# ogn_wind_1_4.net
KiCad netlist of a schematic drawn in EAGLE
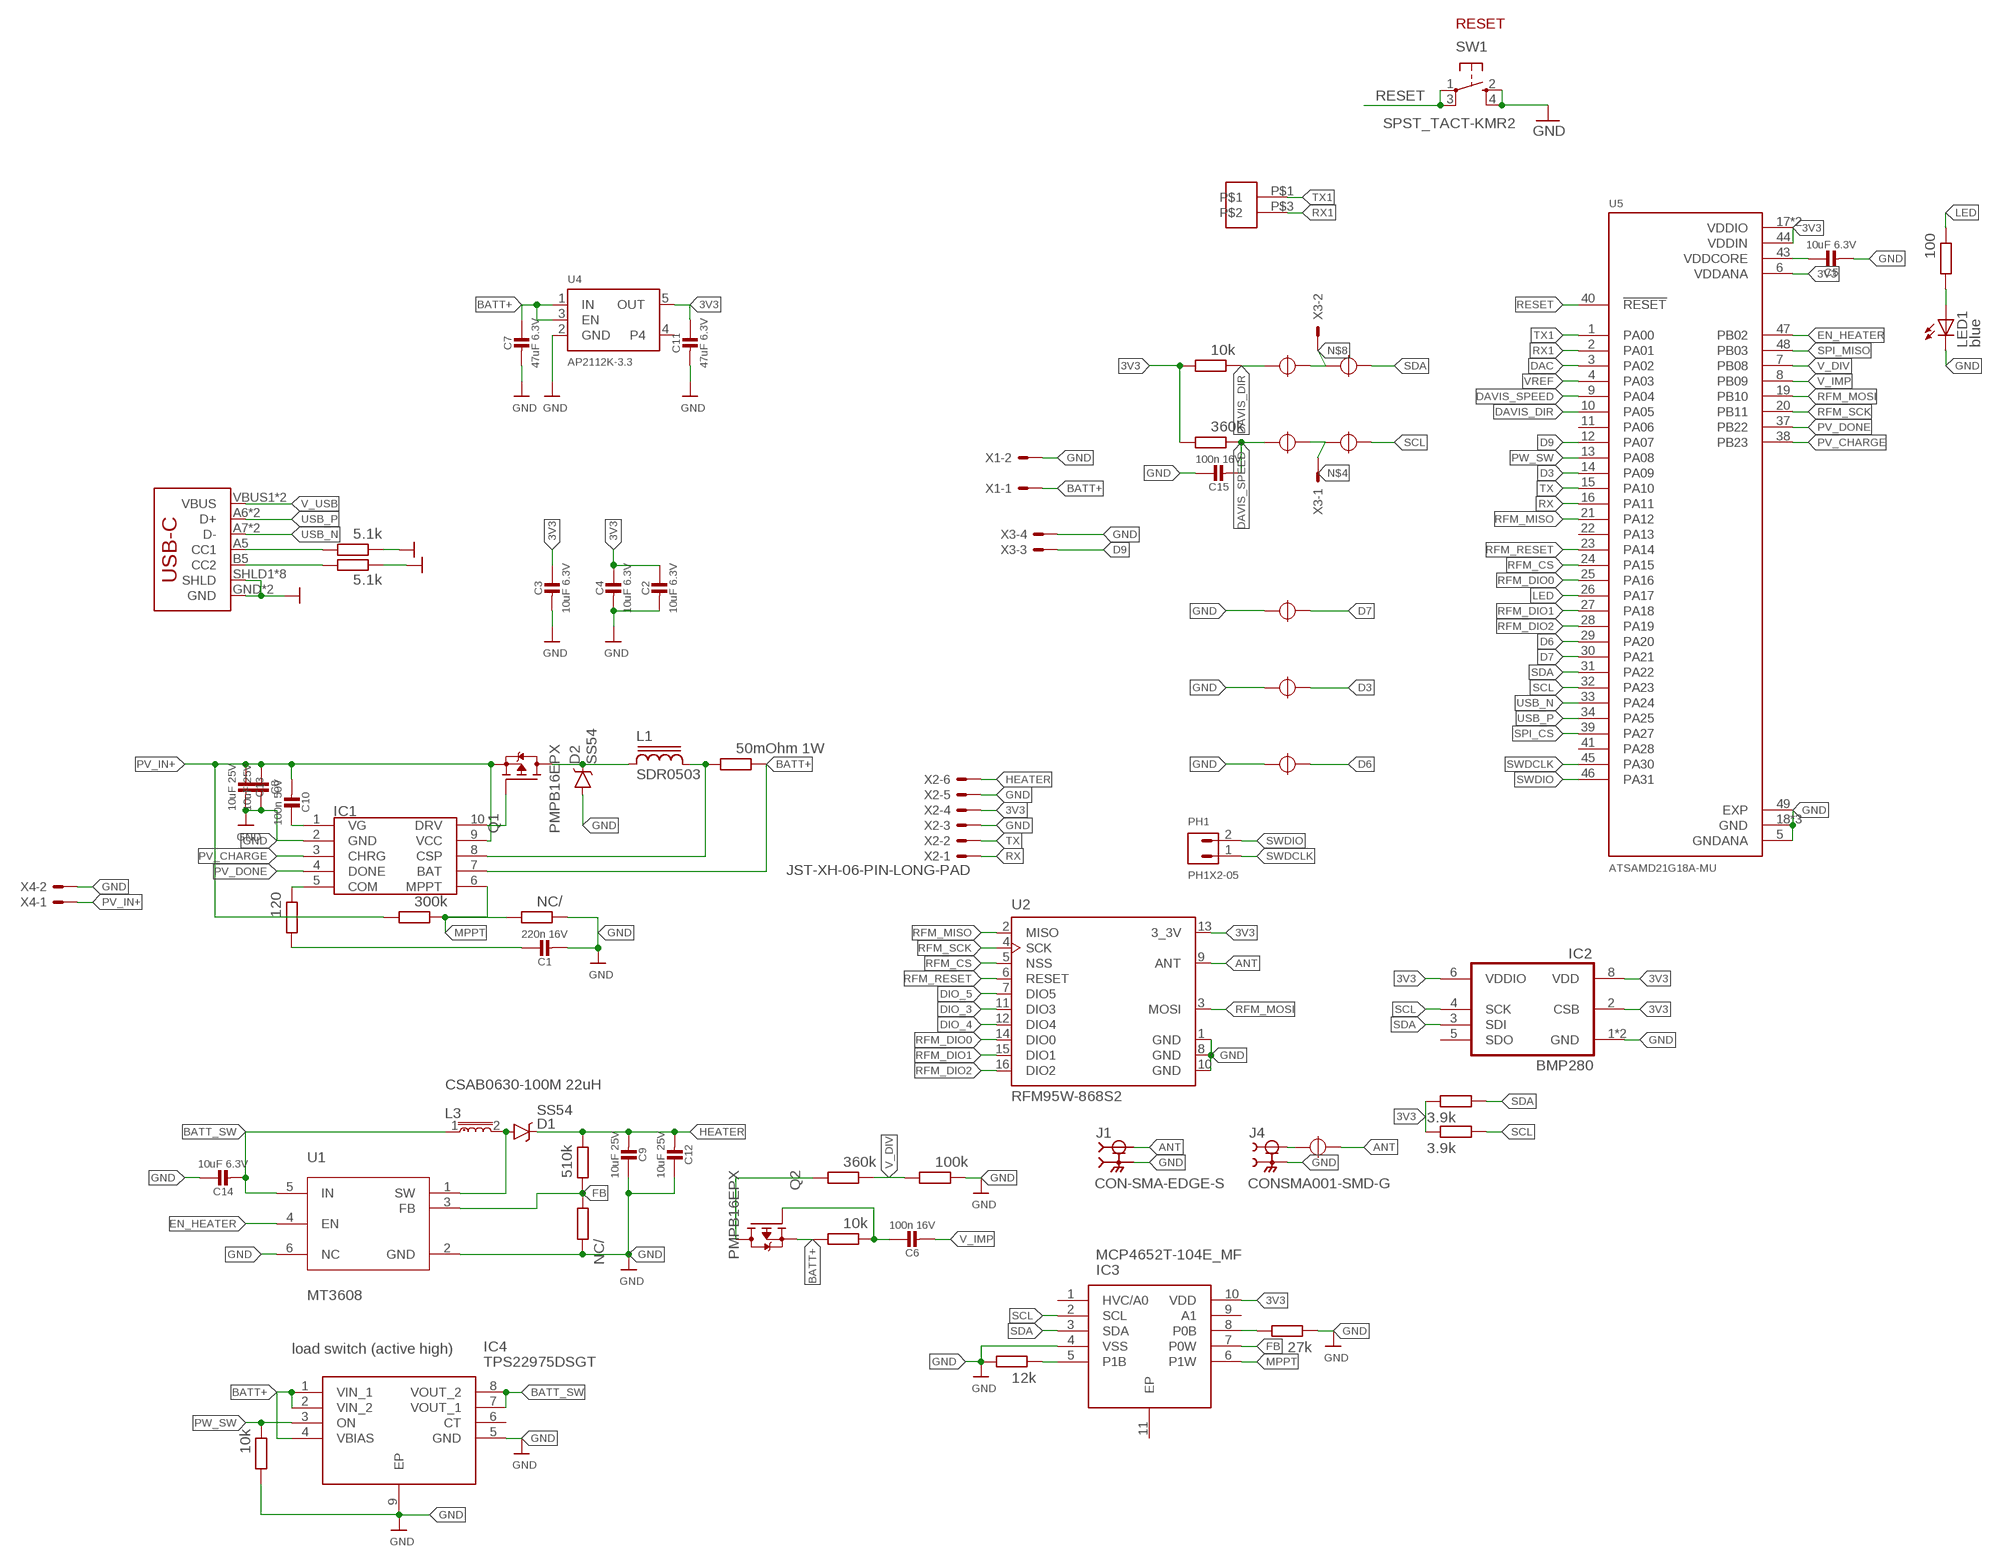
[diagram p0: schematic, sheet 1]

(export (version "E")
  (design (tool "Eeschema 10.0.6"))
  (components
    (comp (ref "C1")
      (value "220n 16V")
      (footprint "eagle-import:_0402MP")
      (libsource (lib "eagle-import") (part "CAP_CERAMIC_0402MP"))
    )
    (comp (ref "C2")
      (value "10uF 6.3V")
      (footprint "eagle-import:_0402MP")
      (libsource (lib "eagle-import") (part "CAP_CERAMIC_0402MP"))
    )
    (comp (ref "C3")
      (value "10uF 6.3V")
      (footprint "eagle-import:_0402MP")
      (libsource (lib "eagle-import") (part "CAP_CERAMIC_0402MP"))
    )
    (comp (ref "C4")
      (value "10uF 6.3V")
      (footprint "eagle-import:_0402MP")
      (libsource (lib "eagle-import") (part "CAP_CERAMIC_0402MP"))
    )
    (comp (ref "C5")
      (value "10uF 6.3V")
      (footprint "eagle-import:_0402MP")
      (libsource (lib "eagle-import") (part "CAP_CERAMIC_0402MP"))
    )
    (comp (ref "C6")
      (value "100n 16V")
      (footprint "eagle-import:_0402MP")
      (fields (field (name "SPICEPREFIX") "C"))
      (libsource (lib "eagle-import") (part "CAP_CERAMIC_0402MP"))
    )
    (comp (ref "C7")
      (value "47uF 6.3V")
      (footprint "eagle-import:0805-NO")
      (libsource (lib "eagle-import") (part "CAP_CERAMIC0805-NOOUTLINE"))
    )
    (comp (ref "C8")
      (value "10uF 25V")
      (footprint "eagle-import:_0603MP")
      (libsource (lib "eagle-import") (part "CAP_CERAMIC_0603MP"))
    )
    (comp (ref "C9")
      (value "10uF 25V")
      (footprint "eagle-import:_0603MP")
      (libsource (lib "eagle-import") (part "CAP_CERAMIC_0603MP"))
    )
    (comp (ref "C10")
      (value "100n 50V")
      (footprint "eagle-import:_0603MP")
      (libsource (lib "eagle-import") (part "CAP_CERAMIC_0603MP"))
    )
    (comp (ref "C11")
      (value "47uF 6.3V")
      (footprint "eagle-import:0805-NO")
      (libsource (lib "eagle-import") (part "CAP_CERAMIC0805-NOOUTLINE"))
    )
    (comp (ref "C12")
      (value "10uF 25V")
      (footprint "eagle-import:_0603MP")
      (libsource (lib "eagle-import") (part "CAP_CERAMIC_0603MP"))
    )
    (comp (ref "C13")
      (value "10uF 25V")
      (footprint "eagle-import:_0603MP")
      (libsource (lib "eagle-import") (part "CAP_CERAMIC_0603MP"))
    )
    (comp (ref "C14")
      (value "10uF 6.3V")
      (footprint "eagle-import:_0402MP")
      (libsource (lib "eagle-import") (part "CAP_CERAMIC_0402MP"))
    )
    (comp (ref "C15")
      (value "100n 16V")
      (footprint "eagle-import:_0402MP")
      (fields (field (name "SPICEPREFIX") "C"))
      (libsource (lib "eagle-import") (part "CAP_CERAMIC_0402MP"))
    )
    (comp (ref "D1")
      (value "SS54")
      (footprint "eagle-import:DO-214AC")
      (fields (field (name "MF") "MDD"))
      (libsource (lib "eagle-import") (part "SS54"))
    )
    (comp (ref "D2")
      (value "SS54")
      (footprint "eagle-import:DO-214AC")
      (fields (field (name "MF") "MDD"))
      (libsource (lib "eagle-import") (part "SS54"))
    )
    (comp (ref "IC1")
      (value "CN3791")
      (footprint "eagle-import:SSOP10")
      (fields (field (name "MF") "Consonance"))
      (libsource (lib "eagle-import") (part "CN3791"))
    )
    (comp (ref "IC2")
      (value "BMP280")
      (footprint "eagle-import:BMP280")
      (libsource (lib "eagle-import") (part "BMP280"))
    )
    (comp (ref "IC3")
      (value "MCP4652T-104E_MF")
      (footprint "eagle-import:SON50P300X300X100-11N")
      (fields
        (field (name "MANUFACTURER_PART_NUMBER") "MCP4652T-104E/MF")
        (field (name "MOUSER2_PART_NUMBER") "579-MCP4652T-104E/MF")
      )
      (libsource (lib "eagle-import") (part "MCP4652T-104E_MF"))
    )
    (comp (ref "IC4")
      (value "TPS22975DSGT")
      (footprint "eagle-import:SON50P200X200X80-9N")
      (fields (field (name "MF") "Texas Instruments"))
      (libsource (lib "eagle-import") (part "TPS22975DSGT"))
    )
    (comp (ref "J1")
      (value "CON-SMA-EDGE-S")
      (footprint "eagle-import:RFSOLUTIONS_CON-SMA-EDGE-S")
      (fields (field (name "MF") "RF Solutions"))
      (libsource (lib "eagle-import") (part "CON-SMA-EDGE-S"))
    )
    (comp (ref "J2")
      (value "USB_C16PIN")
      (footprint "eagle-import:USB-C-16P")
      (libsource (lib "eagle-import") (part "USB_C16PIN"))
    )
    (comp (ref "J4")
      (value "CONSMA001-SMD-G")
      (footprint "eagle-import:LINX_CONSMA001-SMD-G")
      (fields (field (name "MF") "TE Connectivity"))
      (libsource (lib "eagle-import") (part "CONSMA001-SMD-G"))
    )
    (comp (ref "L1")
      (value "SDR0503")
      (footprint "eagle-import:SDR0503")
      (libsource (lib "eagle-import") (part "SDR0503"))
    )
    (comp (ref "L3")
      (value "CSAB0630-100M 22uH")
      (footprint "eagle-import:INDC6060X300")
      (fields (field (name "MF") "Codaca") (field (name "MP") "CSAB0630-100M"))
      (libsource (lib "eagle-import") (part "CSAB0630-100M"))
    )
    (comp (ref "LED1")
      (value "blue")
      (footprint "eagle-import:CHIPLED_0603")
      (libsource (lib "eagle-import") (part "LEDCHIPLED_0603"))
    )
    (comp (ref "PH1")
      (value "PH1X2-05")
      (footprint "eagle-import:PH005-1-2")
      (libsource (lib "eagle-import") (part "PH1X2-05"))
    )
    (comp (ref "Q1")
      (value "PMPB16EPX")
      (footprint "eagle-import:TRANS_PMPB16EPX")
      (fields (field (name "MF") "Nexperia USA Inc.") (field (name "SPICEPREFIX") "Q"))
      (libsource (lib "eagle-import") (part "PMPB16EPX"))
    )
    (comp (ref "Q2")
      (value "PMPB16EPX")
      (footprint "eagle-import:TRANS_PMPB16EPX")
      (fields (field (name "MF") "Nexperia USA Inc."))
      (libsource (lib "eagle-import") (part "PMPB16EPX"))
    )
    (comp (ref "SW1")
      (value "SPST_TACT-KMR2")
      (footprint "eagle-import:KMR2")
      (libsource (lib "eagle-import") (part "SPST_TACT-KMR2"))
    )
    (comp (ref "U$1") (value "SJ") (footprint "eagle-import:SJ") (libsource (lib "eagle-import") (part "SJ")))
    (comp (ref "U$2") (value "SJ") (footprint "eagle-import:SJ") (libsource (lib "eagle-import") (part "SJ")))
    (comp (ref "U$3") (value "SJ") (footprint "eagle-import:SJ") (libsource (lib "eagle-import") (part "SJ")))
    (comp (ref "U$4") (value "SJ") (footprint "eagle-import:SJ") (libsource (lib "eagle-import") (part "SJ")))
    (comp (ref "U$7") (value "SJ") (footprint "eagle-import:SJ") (libsource (lib "eagle-import") (part "SJ")))
    (comp (ref "U$10")
      (value "SJ")
      (footprint "eagle-import:SJ")
      (libsource (lib "eagle-import") (part "SJ"))
    )
    (comp (ref "U$11")
      (value "SJ")
      (footprint "eagle-import:SJ")
      (libsource (lib "eagle-import") (part "SJ"))
    )
    (comp (ref "U$13")
      (value "SMDPAD2")
      (footprint "eagle-import:SMDPAD2")
      (libsource (lib "eagle-import") (part "SMDPAD2"))
    )
    (comp (ref "U$22")
      (value "SJ")
      (footprint "eagle-import:SJ")
      (libsource (lib "eagle-import") (part "SJ"))
    )
    (comp (ref "U1")
      (value "MT3608")
      (footprint "eagle-import:SOT95P280X145-6N")
      (fields (field (name "MF") "Aerosemi Technology Co., Ltd"))
      (libsource (lib "eagle-import") (part "MT3608"))
    )
    (comp (ref "U2")
      (value "RFM95W-868S2")
      (footprint "eagle-import:XCVR_RFM95W-868S2")
      (fields (field (name "MF") "RF"))
      (libsource (lib "eagle-import") (part "RFM95W-868S2"))
    )
    (comp (ref "U4")
      (value "AP2112K-3.3")
      (footprint "eagle-import:SOT23-5")
      (libsource (lib "eagle-import") (part "VREG_SOT23-5"))
    )
    (comp (ref "U5")
      (value "ATSAMD21G18A-MU")
      (footprint "eagle-import:QFN50P700X700X90-49N")
      (fields (field (name "MF") "Microchip"))
      (libsource (lib "eagle-import") (part "ATSAMD21G18A-MU"))
    )
    (comp (ref "USBCR")
      (value "5.1k")
      (footprint "eagle-import:0402RF")
      (libsource (lib "eagle-import") (part "R-EU_R0402RF"))
    )
    (comp (ref "USBCR1")
      (value "5.1k")
      (footprint "eagle-import:0402RF")
      (libsource (lib "eagle-import") (part "R-EU_R0402RF"))
    )
    (comp (ref "USBCR2")
      (value "360k")
      (footprint "eagle-import:0402RF")
      (fields (field (name "SPICEPREFIX") "B"))
      (libsource (lib "eagle-import") (part "R-EU_R0402RF"))
    )
    (comp (ref "USBCR3")
      (value "100k")
      (footprint "eagle-import:0402RF")
      (fields (field (name "SPICEPREFIX") "B"))
      (libsource (lib "eagle-import") (part "R-EU_R0402RF"))
    )
    (comp (ref "USBCR4")
      (value "10k")
      (footprint "eagle-import:0402RF")
      (fields (field (name "SPICEPREFIX") "B"))
      (libsource (lib "eagle-import") (part "R-EU_R0402RF"))
    )
    (comp (ref "USBCR5")
      (value "10k")
      (footprint "eagle-import:0402RF")
      (libsource (lib "eagle-import") (part "R-EU_R0402RF"))
    )
    (comp (ref "USBCR6")
      (value "300k")
      (footprint "eagle-import:0402RF")
      (libsource (lib "eagle-import") (part "R-EU_R0402RF"))
    )
    (comp (ref "USBCR7")
      (value "NC/")
      (footprint "eagle-import:0402RF")
      (libsource (lib "eagle-import") (part "R-EU_R0402RF"))
    )
    (comp (ref "USBCR8")
      (value "120")
      (footprint "eagle-import:0402RF")
      (libsource (lib "eagle-import") (part "R-EU_R0402RF"))
    )
    (comp (ref "USBCR9")
      (value "510k")
      (footprint "eagle-import:0402RF")
      (libsource (lib "eagle-import") (part "R-EU_R0402RF"))
    )
    (comp (ref "USBCR10")
      (value "NC/")
      (footprint "eagle-import:0402RF")
      (libsource (lib "eagle-import") (part "R-EU_R0402RF"))
    )
    (comp (ref "USBCR11")
      (value "10k")
      (footprint "eagle-import:0402RF")
      (libsource (lib "eagle-import") (part "R-EU_R0402RF"))
    )
    (comp (ref "USBCR12")
      (value "360k")
      (footprint "eagle-import:0402RF")
      (libsource (lib "eagle-import") (part "R-EU_R0402RF"))
    )
    (comp (ref "USBCR13")
      (value "100")
      (footprint "eagle-import:0402RF")
      (libsource (lib "eagle-import") (part "R-EU_R0402RF"))
    )
    (comp (ref "USBCR14")
      (value "3.9k")
      (footprint "eagle-import:0402RF")
      (libsource (lib "eagle-import") (part "R-EU_R0402RF"))
    )
    (comp (ref "USBCR15")
      (value "3.9k")
      (footprint "eagle-import:0402RF")
      (libsource (lib "eagle-import") (part "R-EU_R0402RF"))
    )
    (comp (ref "USBCR17")
      (value "27k")
      (footprint "eagle-import:0402RF")
      (libsource (lib "eagle-import") (part "R-EU_R0402RF"))
    )
    (comp (ref "USBCR18")
      (value "12k")
      (footprint "eagle-import:0402RF")
      (libsource (lib "eagle-import") (part "R-EU_R0402RF"))
    )
    (comp (ref "USBCR19")
      (value "50mOhm 1W")
      (footprint "eagle-import:R1206")
      (libsource (lib "eagle-import") (part "R-EU_R1206"))
    )
    (comp (ref "X1")
      (value "JST-XH-02-PIN-LONG-PAD")
      (footprint "eagle-import:JST-XH-02-PACKAGE-LONG-PAD")
      (libsource (lib "eagle-import") (part "JST-XH-02-PIN-LONG-PAD"))
    )
    (comp (ref "X2")
      (value "JST-XH-06-PIN-LONG-PAD")
      (footprint "eagle-import:JST-XH-06-PACKAGE-LONG-PAD")
      (libsource (lib "eagle-import") (part "JST-XH-06-PIN-LONG-PAD"))
    )
    (comp (ref "X3")
      (value "JST-XH-04-PIN-LONG-PAD")
      (footprint "eagle-import:JST-XH-04-PACKAGE-LONG-PAD")
      (libsource (lib "eagle-import") (part "JST-XH-04-PIN-LONG-PAD"))
    )
    (comp (ref "X4")
      (value "JST-XH-02-PIN-LONG-PAD")
      (footprint "eagle-import:JST-XH-02-PACKAGE-LONG-PAD")
      (libsource (lib "eagle-import") (part "JST-XH-02-PIN-LONG-PAD"))
    )
  )
  (nets
    (net (code "1") (name "3V3") (class "Default")
      (node (ref "C11") (pin "1") (pinfunction "1_1") (pintype "passive"))
      (node (ref "C2") (pin "1") (pinfunction "1_1") (pintype "passive"))
      (node (ref "C3") (pin "1") (pinfunction "1_1") (pintype "passive"))
      (node (ref "C4") (pin "1") (pinfunction "1_1") (pintype "passive"))
      (node (ref "IC2") (pin "2") (pinfunction "CSB_2") (pintype "input"))
      (node (ref "IC2") (pin "6") (pinfunction "VDDIO_6") (pintype "power_in"))
      (node (ref "IC2") (pin "8") (pinfunction "VDD_8") (pintype "power_in"))
      (node (ref "IC3") (pin "10") (pinfunction "VDD_10") (pintype "bidirectional"))
      (node (ref "U2") (pin "13") (pinfunction "3_3V_13") (pintype "power_in"))
      (node (ref "U4") (pin "5") (pinfunction "OUT_5") (pintype "power_in"))
      (node (ref "U5") (pin "17") (pinfunction "VDDIO_17") (pintype "power_in"))
      (node (ref "U5") (pin "36") (pinfunction "VDDIO_36") (pintype "power_in"))
      (node (ref "U5") (pin "44") (pinfunction "VDDIN_44") (pintype "power_in"))
      (node (ref "U5") (pin "6") (pinfunction "VDDANA_6") (pintype "power_in"))
      (node (ref "USBCR11") (pin "1") (pinfunction "1_1") (pintype "passive"))
      (node (ref "USBCR12") (pin "1") (pinfunction "1_1") (pintype "passive"))
      (node (ref "USBCR14") (pin "2") (pinfunction "2_2") (pintype "passive"))
      (node (ref "USBCR15") (pin "2") (pinfunction "2_2") (pintype "passive"))
      (node (ref "X2") (pin "4") (pinfunction "S_4") (pintype "passive"))
    )
    (net (code "2") (name "ANT") (class "Default")
      (node (ref "J1") (pin "1") (pinfunction "1_1") (pintype "passive"))
      (node (ref "U$22") (pin "P$2") (pinfunction "P$2_P$2") (pintype "bidirectional"))
      (node (ref "U2") (pin "9") (pinfunction "ANT_9") (pintype "passive"))
    )
    (net (code "3") (name "BATT+") (class "Default")
      (node (ref "C7") (pin "1") (pinfunction "1_1") (pintype "passive"))
      (node (ref "IC1") (pin "7") (pinfunction "BAT_7") (pintype "bidirectional"))
      (node (ref "IC4") (pin "1") (pinfunction "VIN_1_1") (pintype "bidirectional"))
      (node (ref "IC4") (pin "2") (pinfunction "VIN_2_2") (pintype "bidirectional"))
      (node (ref "IC4") (pin "4") (pinfunction "VBIAS_4") (pintype "bidirectional"))
      (node (ref "Q2") (pin "4") (pinfunction "S_4") (pintype "passive"))
      (node (ref "Q2") (pin "8") (pinfunction "S_8") (pintype "passive"))
      (node (ref "U4") (pin "1") (pinfunction "IN_1") (pintype "power_in"))
      (node (ref "U4") (pin "3") (pinfunction "EN_3") (pintype "input"))
      (node (ref "USBCR19") (pin "2") (pinfunction "2_2") (pintype "passive"))
      (node (ref "USBCR4") (pin "1") (pinfunction "1_1") (pintype "passive"))
      (node (ref "X1") (pin "1") (pinfunction "S_1") (pintype "passive"))
    )
    (net (code "4") (name "BATT_SW") (class "Default")
      (node (ref "C14") (pin "2") (pinfunction "2_2") (pintype "passive"))
      (node (ref "IC4") (pin "7") (pinfunction "VOUT_1_7") (pintype "bidirectional"))
      (node (ref "IC4") (pin "8") (pinfunction "VOUT_2_8") (pintype "bidirectional"))
      (node (ref "L3") (pin "1") (pinfunction "1_1") (pintype "passive"))
      (node (ref "U1") (pin "5") (pinfunction "IN_5") (pintype "input"))
    )
    (net (code "5") (name "D3") (class "Default")
      (node (ref "U$10") (pin "P$2") (pinfunction "P$2_P$2") (pintype "bidirectional"))
      (node (ref "U5") (pin "14") (pinfunction "PA09_14") (pintype "bidirectional"))
    )
    (net (code "6") (name "D6") (class "Default")
      (node (ref "U$11") (pin "P$2") (pinfunction "P$2_P$2") (pintype "bidirectional"))
      (node (ref "U5") (pin "29") (pinfunction "PA20_29") (pintype "bidirectional"))
    )
    (net (code "7") (name "D7") (class "Default")
      (node (ref "U$7") (pin "P$2") (pinfunction "P$2_P$2") (pintype "bidirectional"))
      (node (ref "U5") (pin "30") (pinfunction "PA21_30") (pintype "bidirectional"))
    )
    (net (code "8") (name "D9") (class "Default")
      (node (ref "U5") (pin "12") (pinfunction "PA07_12") (pintype "bidirectional"))
      (node (ref "X3") (pin "3") (pinfunction "S_3") (pintype "passive"))
    )
    (net (code "9") (name "DAC") (class "Default")
      (node (ref "U5") (pin "3") (pinfunction "PA02_3") (pintype "bidirectional"))
    )
    (net (code "10") (name "DAVIS_DIR") (class "Default")
      (node (ref "U$3") (pin "P$1") (pinfunction "P$1_P$1") (pintype "bidirectional"))
      (node (ref "U5") (pin "10") (pinfunction "PA05_10") (pintype "bidirectional"))
      (node (ref "USBCR11") (pin "2") (pinfunction "2_2") (pintype "passive"))
    )
    (net (code "11") (name "DAVIS_SPEED") (class "Default")
      (node (ref "C15") (pin "2") (pinfunction "2_2") (pintype "passive"))
      (node (ref "U$1") (pin "P$1") (pinfunction "P$1_P$1") (pintype "bidirectional"))
      (node (ref "U5") (pin "9") (pinfunction "PA04_9") (pintype "bidirectional"))
      (node (ref "USBCR12") (pin "2") (pinfunction "2_2") (pintype "passive"))
    )
    (net (code "12") (name "DIO_3") (class "Default")
      (node (ref "U2") (pin "11") (pinfunction "DIO3_11") (pintype "bidirectional"))
    )
    (net (code "13") (name "DIO_4") (class "Default")
      (node (ref "U2") (pin "12") (pinfunction "DIO4_12") (pintype "bidirectional"))
    )
    (net (code "14") (name "DIO_5") (class "Default")
      (node (ref "U2") (pin "7") (pinfunction "DIO5_7") (pintype "bidirectional"))
    )
    (net (code "15") (name "EN_HEATER") (class "Default")
      (node (ref "U1") (pin "4") (pinfunction "EN_4") (pintype "input"))
      (node (ref "U5") (pin "47") (pinfunction "PB02_47") (pintype "bidirectional"))
    )
    (net (code "16") (name "FB") (class "Default")
      (node (ref "IC3") (pin "7") (pinfunction "P0W_7") (pintype "bidirectional"))
      (node (ref "U1") (pin "3") (pinfunction "FB_3") (pintype "input"))
      (node (ref "USBCR10") (pin "1") (pinfunction "1_1") (pintype "passive"))
      (node (ref "USBCR9") (pin "1") (pinfunction "1_1") (pintype "passive"))
    )
    (net (code "17") (name "GND") (class "Default")
      (node (ref "C1") (pin "2") (pinfunction "2_2") (pintype "passive"))
      (node (ref "C11") (pin "2") (pinfunction "2_2") (pintype "passive"))
      (node (ref "C12") (pin "1") (pinfunction "1_1") (pintype "passive"))
      (node (ref "C13") (pin "2") (pinfunction "2_2") (pintype "passive"))
      (node (ref "C14") (pin "1") (pinfunction "1_1") (pintype "passive"))
      (node (ref "C15") (pin "1") (pinfunction "1_1") (pintype "passive"))
      (node (ref "C2") (pin "2") (pinfunction "2_2") (pintype "passive"))
      (node (ref "C3") (pin "2") (pinfunction "2_2") (pintype "passive"))
      (node (ref "C4") (pin "2") (pinfunction "2_2") (pintype "passive"))
      (node (ref "C5") (pin "2") (pinfunction "2_2") (pintype "passive"))
      (node (ref "C7") (pin "2") (pinfunction "2_2") (pintype "passive"))
      (node (ref "C8") (pin "2") (pinfunction "2_2") (pintype "passive"))
      (node (ref "C9") (pin "1") (pinfunction "1_1") (pintype "passive"))
      (node (ref "D2") (pin "A") (pinfunction "A_A") (pintype "passive"))
      (node (ref "IC1") (pin "2") (pinfunction "GND_2") (pintype "bidirectional"))
      (node (ref "IC2") (pin "1") (pinfunction "GND_1") (pintype "power_in"))
      (node (ref "IC2") (pin "7") (pinfunction "GND_7") (pintype "power_in"))
      (node (ref "IC3") (pin "4") (pinfunction "VSS_4") (pintype "bidirectional"))
      (node (ref "IC4") (pin "5") (pinfunction "GND_5") (pintype "bidirectional"))
      (node (ref "IC4") (pin "9") (pinfunction "EP_9") (pintype "bidirectional"))
      (node (ref "J1") (pin "G1") (pinfunction "2_G1") (pintype "passive"))
      (node (ref "J1") (pin "G2") (pinfunction "2_G2") (pintype "passive"))
      (node (ref "J1") (pin "G3") (pinfunction "2_G3") (pintype "passive"))
      (node (ref "J1") (pin "G4") (pinfunction "2_G4") (pintype "passive"))
      (node (ref "J2") (pin "GND") (pinfunction "GND_GND") (pintype "bidirectional"))
      (node (ref "J2") (pin "GND2") (pinfunction "GND_GND2") (pintype "bidirectional"))
      (node (ref "J2") (pin "SHLD1") (pinfunction "SHLD_SHLD1") (pintype "bidirectional"))
      (node (ref "J2") (pin "SHLD2") (pinfunction "SHLD_SHLD2") (pintype "bidirectional"))
      (node (ref "J2") (pin "SHLD3") (pinfunction "SHLD_SHLD3") (pintype "bidirectional"))
      (node (ref "J2") (pin "SHLD4") (pinfunction "SHLD_SHLD4") (pintype "bidirectional"))
      (node (ref "J2") (pin "SHLD5") (pinfunction "SHLD_SHLD5") (pintype "bidirectional"))
      (node (ref "J2") (pin "SHLD6") (pinfunction "SHLD_SHLD6") (pintype "bidirectional"))
      (node (ref "J2") (pin "SHLD7") (pinfunction "SHLD_SHLD7") (pintype "bidirectional"))
      (node (ref "J2") (pin "SHLD8") (pinfunction "SHLD_SHLD8") (pintype "bidirectional"))
      (node (ref "J4") (pin "S1") (pinfunction "2_S1") (pintype "passive"))
      (node (ref "J4") (pin "S2") (pinfunction "2_S2") (pintype "passive"))
      (node (ref "LED1") (pin "C") (pinfunction "C_C") (pintype "passive"))
      (node (ref "SW1") (pin "2") (pinfunction "S_2") (pintype "passive"))
      (node (ref "SW1") (pin "4") (pinfunction "S1_4") (pintype "passive"))
      (node (ref "U$10") (pin "P$1") (pinfunction "P$1_P$1") (pintype "bidirectional"))
      (node (ref "U$11") (pin "P$1") (pinfunction "P$1_P$1") (pintype "bidirectional"))
      (node (ref "U$7") (pin "P$1") (pinfunction "P$1_P$1") (pintype "bidirectional"))
      (node (ref "U1") (pin "2") (pinfunction "GND_2") (pintype "power_in"))
      (node (ref "U1") (pin "6") (pinfunction "NC_6") (pintype "bidirectional"))
      (node (ref "U2") (pin "1") (pinfunction "GND_1") (pintype "power_in"))
      (node (ref "U2") (pin "10") (pinfunction "GND_10") (pintype "power_in"))
      (node (ref "U2") (pin "8") (pinfunction "GND_8") (pintype "power_in"))
      (node (ref "U4") (pin "2") (pinfunction "GND_2") (pintype "power_in"))
      (node (ref "U5") (pin "18") (pinfunction "GND_18") (pintype "power_in"))
      (node (ref "U5") (pin "35") (pinfunction "GND_35") (pintype "power_in"))
      (node (ref "U5") (pin "42") (pinfunction "GND_42") (pintype "power_in"))
      (node (ref "U5") (pin "49") (pinfunction "EXP_49") (pintype "power_in"))
      (node (ref "U5") (pin "5") (pinfunction "GNDANA_5") (pintype "power_in"))
      (node (ref "USBCR") (pin "2") (pinfunction "2_2") (pintype "passive"))
      (node (ref "USBCR1") (pin "2") (pinfunction "2_2") (pintype "passive"))
      (node (ref "USBCR10") (pin "2") (pinfunction "2_2") (pintype "passive"))
      (node (ref "USBCR17") (pin "2") (pinfunction "2_2") (pintype "passive"))
      (node (ref "USBCR18") (pin "1") (pinfunction "1_1") (pintype "passive"))
      (node (ref "USBCR3") (pin "2") (pinfunction "2_2") (pintype "passive"))
      (node (ref "USBCR5") (pin "1") (pinfunction "1_1") (pintype "passive"))
      (node (ref "USBCR7") (pin "2") (pinfunction "2_2") (pintype "passive"))
      (node (ref "X1") (pin "2") (pinfunction "S_2") (pintype "passive"))
      (node (ref "X2") (pin "3") (pinfunction "S_3") (pintype "passive"))
      (node (ref "X2") (pin "5") (pinfunction "S_5") (pintype "passive"))
      (node (ref "X3") (pin "4") (pinfunction "S_4") (pintype "passive"))
      (node (ref "X4") (pin "2") (pinfunction "S_2") (pintype "passive"))
    )
    (net (code "18") (name "HEATER") (class "Default")
      (node (ref "C12") (pin "2") (pinfunction "2_2") (pintype "passive"))
      (node (ref "C9") (pin "2") (pinfunction "2_2") (pintype "passive"))
      (node (ref "D1") (pin "C") (pinfunction "C_C") (pintype "passive"))
      (node (ref "USBCR9") (pin "2") (pinfunction "2_2") (pintype "passive"))
      (node (ref "X2") (pin "6") (pinfunction "S_6") (pintype "passive"))
    )
    (net (code "19") (name "LED") (class "Default")
      (node (ref "U5") (pin "26") (pinfunction "PA17_26") (pintype "bidirectional"))
      (node (ref "USBCR13") (pin "2") (pinfunction "2_2") (pintype "passive"))
    )
    (net (code "20") (name "MPPT") (class "Default")
      (node (ref "IC1") (pin "6") (pinfunction "MPPT_6") (pintype "bidirectional"))
      (node (ref "IC3") (pin "6") (pinfunction "P1W_6") (pintype "bidirectional"))
      (node (ref "USBCR6") (pin "2") (pinfunction "2_2") (pintype "passive"))
      (node (ref "USBCR7") (pin "1") (pinfunction "1_1") (pintype "passive"))
    )
    (net (code "21") (name "N$4") (class "Default")
      (node (ref "U$1") (pin "P$2") (pinfunction "P$2_P$2") (pintype "bidirectional"))
      (node (ref "U$2") (pin "P$1") (pinfunction "P$1_P$1") (pintype "bidirectional"))
      (node (ref "X3") (pin "1") (pinfunction "S_1") (pintype "passive"))
    )
    (net (code "22") (name "N$8") (class "Default")
      (node (ref "U$3") (pin "P$2") (pinfunction "P$2_P$2") (pintype "bidirectional"))
      (node (ref "U$4") (pin "P$1") (pinfunction "P$1_P$1") (pintype "bidirectional"))
      (node (ref "X3") (pin "2") (pinfunction "S_2") (pintype "passive"))
    )
    (net (code "23") (name "Net-(C1-Pad1)") (class "Default")
      (node (ref "C1") (pin "1") (pinfunction "1_1") (pintype "passive"))
      (node (ref "USBCR8") (pin "1") (pinfunction "1_1") (pintype "passive"))
    )
    (net (code "24") (name "Net-(D2-PadC)") (class "Default")
      (node (ref "D2") (pin "C") (pinfunction "C_C") (pintype "passive"))
      (node (ref "L1") (pin "1") (pinfunction "1_1") (pintype "passive"))
      (node (ref "Q1") (pin "1") (pinfunction "D_1") (pintype "passive"))
      (node (ref "Q1") (pin "2") (pinfunction "D_2") (pintype "passive"))
      (node (ref "Q1") (pin "5") (pinfunction "D_5") (pintype "passive"))
      (node (ref "Q1") (pin "6") (pinfunction "D_6") (pintype "passive"))
      (node (ref "Q1") (pin "7") (pinfunction "D_7") (pintype "passive"))
    )
    (net (code "25") (name "Net-(IC1-COM)") (class "Default")
      (node (ref "IC1") (pin "5") (pinfunction "COM_5") (pintype "bidirectional"))
      (node (ref "USBCR8") (pin "2") (pinfunction "2_2") (pintype "passive"))
    )
    (net (code "26") (name "Net-(IC1-CSP)") (class "Default")
      (node (ref "IC1") (pin "8") (pinfunction "CSP_8") (pintype "bidirectional"))
      (node (ref "L1") (pin "2") (pinfunction "2_2") (pintype "passive"))
      (node (ref "USBCR19") (pin "1") (pinfunction "1_1") (pintype "passive"))
    )
    (net (code "27") (name "Net-(IC1-DRV)") (class "Default")
      (node (ref "IC1") (pin "10") (pinfunction "DRV_10") (pintype "bidirectional"))
      (node (ref "Q1") (pin "3") (pinfunction "G_3") (pintype "passive"))
    )
    (net (code "28") (name "Net-(IC1-VG)") (class "Default")
      (node (ref "C10") (pin "1") (pinfunction "1_1") (pintype "passive"))
      (node (ref "IC1") (pin "1") (pinfunction "VG_1") (pintype "bidirectional"))
    )
    (net (code "29") (name "Net-(IC3-P0B)") (class "Default")
      (node (ref "IC3") (pin "8") (pinfunction "P0B_8") (pintype "bidirectional"))
      (node (ref "USBCR17") (pin "1") (pinfunction "1_1") (pintype "passive"))
    )
    (net (code "30") (name "Net-(IC3-P1B)") (class "Default")
      (node (ref "IC3") (pin "5") (pinfunction "P1B_5") (pintype "bidirectional"))
      (node (ref "USBCR18") (pin "2") (pinfunction "2_2") (pintype "passive"))
    )
    (net (code "31") (name "Net-(J2-CC1)") (class "Default")
      (node (ref "J2") (pin "A5") (pinfunction "CC1_A5") (pintype "bidirectional"))
      (node (ref "USBCR") (pin "1") (pinfunction "1_1") (pintype "passive"))
    )
    (net (code "32") (name "Net-(J2-CC2)") (class "Default")
      (node (ref "J2") (pin "B5") (pinfunction "CC2_B5") (pintype "bidirectional"))
      (node (ref "USBCR1") (pin "1") (pinfunction "1_1") (pintype "passive"))
    )
    (net (code "33") (name "Net-(J4-Pad1)") (class "Default")
      (node (ref "J4") (pin "1") (pinfunction "1_1") (pintype "passive"))
      (node (ref "U$22") (pin "P$1") (pinfunction "P$1_P$1") (pintype "bidirectional"))
    )
    (net (code "34") (name "Net-(LED1-PadA)") (class "Default")
      (node (ref "LED1") (pin "A") (pinfunction "A_A") (pintype "passive"))
      (node (ref "USBCR13") (pin "1") (pinfunction "1_1") (pintype "passive"))
    )
    (net (code "35") (name "Net-(Q2-D-Pad1)") (class "Default")
      (node (ref "Q2") (pin "1") (pinfunction "D_1") (pintype "passive"))
      (node (ref "Q2") (pin "2") (pinfunction "D_2") (pintype "passive"))
      (node (ref "Q2") (pin "5") (pinfunction "D_5") (pintype "passive"))
      (node (ref "Q2") (pin "6") (pinfunction "D_6") (pintype "passive"))
      (node (ref "Q2") (pin "7") (pinfunction "D_7") (pintype "passive"))
      (node (ref "USBCR2") (pin "1") (pinfunction "1_1") (pintype "passive"))
    )
    (net (code "36") (name "Net-(Q2-G)") (class "Default")
      (node (ref "C6") (pin "1") (pinfunction "1_1") (pintype "passive"))
      (node (ref "Q2") (pin "3") (pinfunction "G_3") (pintype "passive"))
      (node (ref "USBCR4") (pin "2") (pinfunction "2_2") (pintype "passive"))
    )
    (net (code "37") (name "Net-(U1-SW)") (class "Default")
      (node (ref "D1") (pin "A") (pinfunction "A_A") (pintype "passive"))
      (node (ref "L3") (pin "2") (pinfunction "2_2") (pintype "passive"))
      (node (ref "U1") (pin "1") (pinfunction "SW_1") (pintype "output"))
    )
    (net (code "38") (name "Net-(U5-VDDCORE)") (class "Default")
      (node (ref "C5") (pin "1") (pinfunction "1_1") (pintype "passive"))
      (node (ref "U5") (pin "43") (pinfunction "VDDCORE_43") (pintype "power_in"))
    )
    (net (code "39") (name "PV_CHARGE") (class "Default")
      (node (ref "IC1") (pin "3") (pinfunction "CHRG_3") (pintype "bidirectional"))
      (node (ref "U5") (pin "38") (pinfunction "PB23_38") (pintype "bidirectional"))
    )
    (net (code "40") (name "PV_DONE") (class "Default")
      (node (ref "IC1") (pin "4") (pinfunction "DONE_4") (pintype "bidirectional"))
      (node (ref "U5") (pin "37") (pinfunction "PB22_37") (pintype "bidirectional"))
    )
    (net (code "41") (name "PV_IN+") (class "Default")
      (node (ref "C10") (pin "2") (pinfunction "2_2") (pintype "passive"))
      (node (ref "C13") (pin "1") (pinfunction "1_1") (pintype "passive"))
      (node (ref "C8") (pin "1") (pinfunction "1_1") (pintype "passive"))
      (node (ref "IC1") (pin "9") (pinfunction "VCC_9") (pintype "bidirectional"))
      (node (ref "Q1") (pin "4") (pinfunction "S_4") (pintype "passive"))
      (node (ref "Q1") (pin "8") (pinfunction "S_8") (pintype "passive"))
      (node (ref "USBCR6") (pin "1") (pinfunction "1_1") (pintype "passive"))
      (node (ref "X4") (pin "1") (pinfunction "S_1") (pintype "passive"))
    )
    (net (code "42") (name "PW_SW") (class "Default")
      (node (ref "IC4") (pin "3") (pinfunction "ON_3") (pintype "bidirectional"))
      (node (ref "U5") (pin "13") (pinfunction "PA08_13") (pintype "bidirectional"))
      (node (ref "USBCR5") (pin "2") (pinfunction "2_2") (pintype "passive"))
    )
    (net (code "43") (name "RESET") (class "Default")
      (node (ref "SW1") (pin "1") (pinfunction "P_1") (pintype "passive"))
      (node (ref "SW1") (pin "3") (pinfunction "P1_3") (pintype "passive"))
      (node (ref "U5") (pin "40") (pinfunction "~{RESET}_40") (pintype "input"))
    )
    (net (code "44") (name "RFM_CS") (class "Default")
      (node (ref "U2") (pin "5") (pinfunction "NSS_5") (pintype "input"))
      (node (ref "U5") (pin "24") (pinfunction "PA15_24") (pintype "bidirectional"))
    )
    (net (code "45") (name "RFM_DIO0") (class "Default")
      (node (ref "U2") (pin "14") (pinfunction "DIO0_14") (pintype "bidirectional"))
      (node (ref "U5") (pin "25") (pinfunction "PA16_25") (pintype "bidirectional"))
    )
    (net (code "46") (name "RFM_DIO1") (class "Default")
      (node (ref "U2") (pin "15") (pinfunction "DIO1_15") (pintype "bidirectional"))
      (node (ref "U5") (pin "27") (pinfunction "PA18_27") (pintype "bidirectional"))
    )
    (net (code "47") (name "RFM_DIO2") (class "Default")
      (node (ref "U2") (pin "16") (pinfunction "DIO2_16") (pintype "bidirectional"))
      (node (ref "U5") (pin "28") (pinfunction "PA19_28") (pintype "bidirectional"))
    )
    (net (code "48") (name "RFM_MISO") (class "Default")
      (node (ref "U2") (pin "2") (pinfunction "MISO_2") (pintype "input"))
      (node (ref "U5") (pin "21") (pinfunction "PA12_21") (pintype "bidirectional"))
    )
    (net (code "49") (name "RFM_MOSI") (class "Default")
      (node (ref "U2") (pin "3") (pinfunction "MOSI_3") (pintype "output"))
      (node (ref "U5") (pin "19") (pinfunction "PB10_19") (pintype "bidirectional"))
    )
    (net (code "50") (name "RFM_RESET") (class "Default")
      (node (ref "U2") (pin "6") (pinfunction "RESET_6") (pintype "bidirectional"))
      (node (ref "U5") (pin "23") (pinfunction "PA14_23") (pintype "bidirectional"))
    )
    (net (code "51") (name "RFM_SCK") (class "Default")
      (node (ref "U2") (pin "4") (pinfunction "SCK_4") (pintype "input"))
      (node (ref "U5") (pin "20") (pinfunction "PB11_20") (pintype "bidirectional"))
    )
    (net (code "52") (name "RX") (class "Default")
      (node (ref "U5") (pin "16") (pinfunction "PA11_16") (pintype "bidirectional"))
      (node (ref "X2") (pin "1") (pinfunction "S_1") (pintype "passive"))
    )
    (net (code "53") (name "RX1") (class "Default")
      (node (ref "U$13") (pin "P$3") (pinfunction "P$2_P$3") (pintype "bidirectional"))
      (node (ref "U5") (pin "2") (pinfunction "PA01_2") (pintype "bidirectional"))
    )
    (net (code "54") (name "SCL") (class "Default")
      (node (ref "IC2") (pin "4") (pinfunction "SCK_4") (pintype "bidirectional"))
      (node (ref "IC3") (pin "2") (pinfunction "SCL_2") (pintype "bidirectional"))
      (node (ref "U$2") (pin "P$2") (pinfunction "P$2_P$2") (pintype "bidirectional"))
      (node (ref "U5") (pin "32") (pinfunction "PA23_32") (pintype "bidirectional"))
      (node (ref "USBCR15") (pin "1") (pinfunction "1_1") (pintype "passive"))
    )
    (net (code "55") (name "SDA") (class "Default")
      (node (ref "IC2") (pin "3") (pinfunction "SDI_3") (pintype "bidirectional"))
      (node (ref "IC3") (pin "3") (pinfunction "SDA_3") (pintype "bidirectional"))
      (node (ref "U$4") (pin "P$2") (pinfunction "P$2_P$2") (pintype "bidirectional"))
      (node (ref "U5") (pin "31") (pinfunction "PA22_31") (pintype "bidirectional"))
      (node (ref "USBCR14") (pin "1") (pinfunction "1_1") (pintype "passive"))
    )
    (net (code "56") (name "SPI_CS") (class "Default")
      (node (ref "U5") (pin "39") (pinfunction "PA27_39") (pintype "bidirectional"))
    )
    (net (code "57") (name "SPI_MISO") (class "Default")
      (node (ref "U5") (pin "48") (pinfunction "PB03_48") (pintype "bidirectional"))
    )
    (net (code "58") (name "SWDCLK") (class "Default")
      (node (ref "PH1") (pin "1") (pinfunction "1_1") (pintype "bidirectional"))
      (node (ref "U5") (pin "45") (pinfunction "PA30_45") (pintype "bidirectional"))
    )
    (net (code "59") (name "SWDIO") (class "Default")
      (node (ref "PH1") (pin "2") (pinfunction "2_2") (pintype "bidirectional"))
      (node (ref "U5") (pin "46") (pinfunction "PA31_46") (pintype "bidirectional"))
    )
    (net (code "60") (name "TX") (class "Default")
      (node (ref "U5") (pin "15") (pinfunction "PA10_15") (pintype "bidirectional"))
      (node (ref "X2") (pin "2") (pinfunction "S_2") (pintype "passive"))
    )
    (net (code "61") (name "TX1") (class "Default")
      (node (ref "U$13") (pin "P$1") (pinfunction "P$1_P$1") (pintype "bidirectional"))
      (node (ref "U5") (pin "1") (pinfunction "PA00_1") (pintype "bidirectional"))
    )
    (net (code "62") (name "USB_N") (class "Default")
      (node (ref "J2") (pin "A7") (pinfunction "D-_A7") (pintype "bidirectional"))
      (node (ref "J2") (pin "B7") (pinfunction "D-_B7") (pintype "bidirectional"))
      (node (ref "U5") (pin "33") (pinfunction "PA24_33") (pintype "bidirectional"))
    )
    (net (code "63") (name "USB_P") (class "Default")
      (node (ref "J2") (pin "A6") (pinfunction "D+_A6") (pintype "bidirectional"))
      (node (ref "J2") (pin "B6") (pinfunction "D+_B6") (pintype "bidirectional"))
      (node (ref "U5") (pin "34") (pinfunction "PA25_34") (pintype "bidirectional"))
    )
    (net (code "64") (name "VREF") (class "Default")
      (node (ref "U5") (pin "4") (pinfunction "PA03_4") (pintype "bidirectional"))
    )
    (net (code "65") (name "V_DIV") (class "Default")
      (node (ref "U5") (pin "7") (pinfunction "PB08_7") (pintype "bidirectional"))
      (node (ref "USBCR2") (pin "2") (pinfunction "2_2") (pintype "passive"))
      (node (ref "USBCR3") (pin "1") (pinfunction "1_1") (pintype "passive"))
    )
    (net (code "66") (name "V_IMP") (class "Default")
      (node (ref "C6") (pin "2") (pinfunction "2_2") (pintype "passive"))
      (node (ref "U5") (pin "8") (pinfunction "PB09_8") (pintype "bidirectional"))
    )
    (net (code "67") (name "V_USB") (class "Default")
      (node (ref "J2") (pin "VBUS1") (pinfunction "VBUS_VBUS1") (pintype "bidirectional"))
      (node (ref "J2") (pin "VBUS2") (pinfunction "VBUS_VBUS2") (pintype "bidirectional"))
    )
    (net (code "68") (name "unconnected-(IC2-SDO-Pad5)") (class "Default")
      (node (ref "IC2") (pin "5") (pinfunction "SDO_5") (pintype "input"))
    )
    (net (code "69") (name "unconnected-(IC3-A1-Pad9)") (class "Default")
      (node (ref "IC3") (pin "9") (pinfunction "A1_9") (pintype "bidirectional"))
    )
    (net (code "70") (name "unconnected-(IC3-EP-Pad11)") (class "Default")
      (node (ref "IC3") (pin "11") (pinfunction "EP_11") (pintype "bidirectional"))
    )
    (net (code "71") (name "unconnected-(IC3-HVC{slash}A0-Pad1)") (class "Default")
      (node (ref "IC3") (pin "1") (pinfunction "HVC/A0_1") (pintype "bidirectional"))
    )
    (net (code "72") (name "unconnected-(IC4-CT-Pad6)") (class "Default")
      (node (ref "IC4") (pin "6") (pinfunction "CT_6") (pintype "bidirectional"))
    )
    (net (code "73") (name "unconnected-(U4-P4-Pad4)") (class "Default")
      (node (ref "U4") (pin "4") (pinfunction "P4_4") (pintype "bidirectional"))
    )
    (net (code "74") (name "unconnected-(U5-PA06-Pad11)") (class "Default")
      (node (ref "U5") (pin "11") (pinfunction "PA06_11") (pintype "bidirectional"))
    )
    (net (code "75") (name "unconnected-(U5-PA13-Pad22)") (class "Default")
      (node (ref "U5") (pin "22") (pinfunction "PA13_22") (pintype "bidirectional"))
    )
    (net (code "76") (name "unconnected-(U5-PA28-Pad41)") (class "Default")
      (node (ref "U5") (pin "41") (pinfunction "PA28_41") (pintype "bidirectional"))
    )
  )
)
